# Power_board_1.net
KiCad netlist of a schematic drawn in Altium Designer
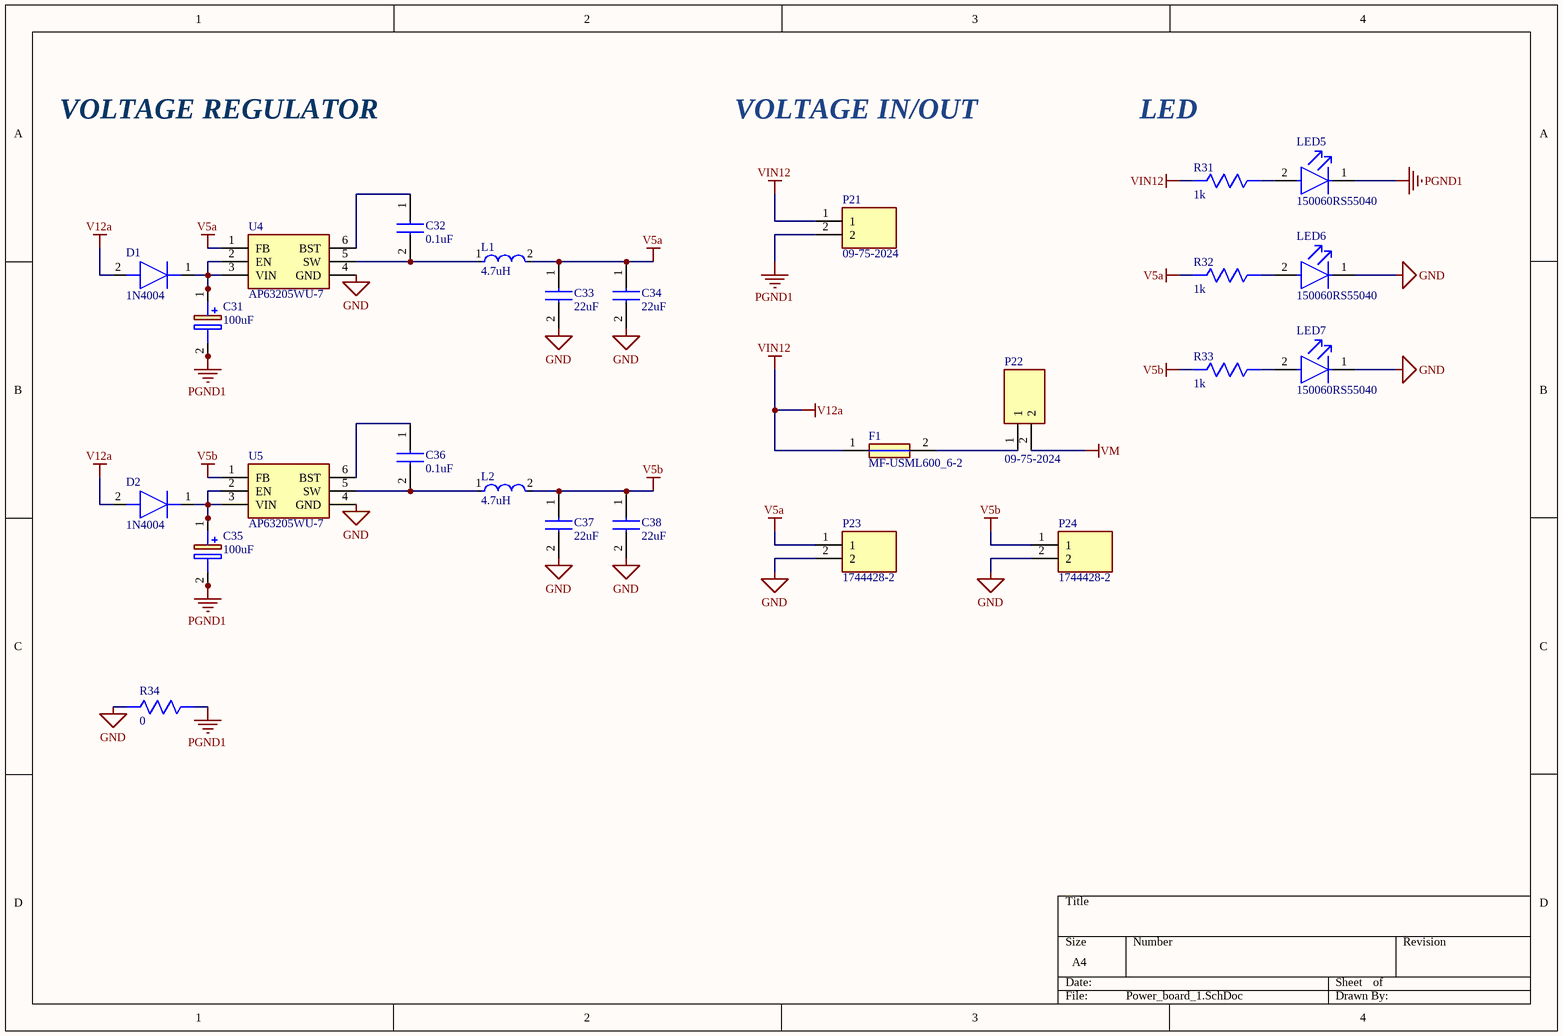
[diagram p0: Power_board_1.SchDoc]

(export (version "E")
  (design (tool "Eeschema 10.0.6"))
  (components
    (comp (ref "C31")
      (value "100uF")
      (footprint "SamacSys:CAPPM7344X310N")
      (description "Capacitor Polarised")
      (fields
        (field (name "MANUFACTURER_PART_NUMBER") "TAJD107K016RNJ")
        (field (name "MOUSER PART NUMBER") "581-TAJD107K016R")
      )
      (libsource (lib "*") (part "TAJD107K016RNJ"))
    )
    (comp (ref "C32")
      (value "0.1uF")
      (footprint "SamacSys:CAPC1608X90N")
      (description "Capacitor")
      (fields
        (field (name "MANUFACTURER_PART_NUMBER") "GRM188R72A104MA35D")
        (field (name "MOUSER PART NUMBER") "81-GRM188R72A104MA5D")
      )
      (libsource (lib "*") (part "GRM188R72A104MA35D"))
    )
    (comp (ref "C33")
      (value "22uF")
      (footprint "SamacSys:C1608_Commercial")
      (description "Capacitor")
      (fields (field (name "MANUFACTURER_PART_NUMBER") "C1608X5R1H104M080AA"))
      (libsource (lib "SamacSys") (part "C1608X5R1H104M080AA"))
    )
    (comp (ref "C34")
      (value "22uF")
      (footprint "SamacSys:C1608_Commercial")
      (description "Capacitor")
      (fields (field (name "MANUFACTURER_PART_NUMBER") "C1608X5R1H104M080AA"))
      (libsource (lib "SamacSys") (part "C1608X5R1H104M080AA"))
    )
    (comp (ref "C35")
      (value "100uF")
      (footprint "SamacSys:CAPPM7344X310N")
      (description "Capacitor Polarised")
      (fields
        (field (name "MANUFACTURER_PART_NUMBER") "TAJD107K016RNJ")
        (field (name "MOUSER PART NUMBER") "581-TAJD107K016R")
      )
      (libsource (lib "*") (part "TAJD107K016RNJ"))
    )
    (comp (ref "C36")
      (value "0.1uF")
      (footprint "SamacSys:CAPC1608X90N")
      (description "Capacitor")
      (fields
        (field (name "MANUFACTURER_PART_NUMBER") "GRM188R72A104MA35D")
        (field (name "MOUSER PART NUMBER") "81-GRM188R72A104MA5D")
      )
      (libsource (lib "*") (part "GRM188R72A104MA35D"))
    )
    (comp (ref "C37")
      (value "22uF")
      (footprint "SamacSys:C1608_Commercial")
      (description "Capacitor")
      (fields (field (name "MANUFACTURER_PART_NUMBER") "C1608X5R1H104M080AA"))
      (libsource (lib "SamacSys") (part "C1608X5R1H104M080AA"))
    )
    (comp (ref "C38")
      (value "22uF")
      (footprint "SamacSys:C1608_Commercial")
      (description "Capacitor")
      (fields (field (name "MANUFACTURER_PART_NUMBER") "C1608X5R1H104M080AA"))
      (libsource (lib "SamacSys") (part "C1608X5R1H104M080AA"))
    )
    (comp (ref "D1")
      (value "1N4004")
      (footprint "SamacSys:DIOAD1413W86L463D238")
      (description "Diode")
      (fields (field (name "MOUSER PART NUMBER") "863-1N4004"))
      (libsource (lib "*") (part "1N4004"))
    )
    (comp (ref "D2")
      (value "1N4004")
      (footprint "SamacSys:DIOAD1413W86L463D238")
      (description "Diode")
      (fields (field (name "MOUSER PART NUMBER") "863-1N4004"))
      (libsource (lib "*") (part "1N4004"))
    )
    (comp (ref "F1")
      (value "MF-USML600_6-2")
      (footprint "SamacSys:FUSC3226X120N")
      (description "Fuse")
      (fields
        (field (name "MANUFACTURER_PART_NUMBER") "MF-USML600/6-2")
        (field (name "MOUSER PART NUMBER") "652-MF-USML600/6-2")
      )
      (libsource (lib "*") (part "MF-USML600_6-2"))
    )
    (comp (ref "L1")
      (value "4.7uH")
      (footprint "FP-NR6028-MFG")
      (description "SMD Power Inductors for Automotive Applications 4.7uH ±20% 2.7A 40.3mΩ")
      (fields (field (name "TOLERANCE") "20%"))
      (libsource (lib "Altium Content Vault") (part "725321dda6339637d4d059423bc1c3c"))
    )
    (comp (ref "L2")
      (value "4.7uH")
      (footprint "FP-NR6028-MFG")
      (description "SMD Power Inductors for Automotive Applications 4.7uH ±20% 2.7A 40.3mΩ")
      (fields (field (name "TOLERANCE") "20%"))
      (libsource (lib "Altium Content Vault") (part "725321dda6339637d4d059423bc1c3c"))
    )
    (comp (ref "LED5")
      (value "150060RS55040")
      (footprint "FP-150060RS55040-MFG")
      (description "LED RED DIFFUSED 0603 SMD")
      (libsource (lib "Altium Content Vault") (part "8706943c75ba83719d021d2fdc84c58"))
    )
    (comp (ref "LED6")
      (value "150060RS55040")
      (footprint "FP-150060RS55040-MFG")
      (description "LED RED DIFFUSED 0603 SMD")
      (libsource (lib "Altium Content Vault") (part "8706943c75ba83719d021d2fdc84c58"))
    )
    (comp (ref "LED7")
      (value "150060RS55040")
      (footprint "FP-150060RS55040-MFG")
      (description "LED RED DIFFUSED 0603 SMD")
      (libsource (lib "Altium Content Vault") (part "8706943c75ba83719d021d2fdc84c58"))
    )
    (comp (ref "P21")
      (value "09-75-2024")
      (footprint "SamacSys:17444282")
      (description "Connector")
      (fields
        (field (name "MANUFACTURER_PART_NUMBER") "1744428-2")
        (field (name "MOUSER PART NUMBER") "571-1744428-2")
      )
      (libsource (lib "SamacSys") (part "1744428-2"))
    )
    (comp (ref "P22")
      (value "09-75-2024")
      (footprint "SamacSys:17444282")
      (description "Connector")
      (fields
        (field (name "MANUFACTURER_PART_NUMBER") "1744428-2")
        (field (name "MOUSER PART NUMBER") "571-1744428-2")
      )
      (libsource (lib "") (part "1744428-2_1"))
    )
    (comp (ref "P23")
      (value "1744428-2")
      (footprint "SamacSys:17444282")
      (description "Connector")
      (fields (field (name "MOUSER PART NUMBER") "571-1744428-2"))
      (libsource (lib "SamacSys") (part "1744428-2"))
    )
    (comp (ref "P24")
      (value "1744428-2")
      (footprint "SamacSys:17444282")
      (description "Connector")
      (fields (field (name "MOUSER PART NUMBER") "571-1744428-2"))
      (libsource (lib "SamacSys") (part "1744428-2"))
    )
    (comp (ref "R31")
      (value "1k")
      (footprint "SamacSys:RESC1608X55N")
      (description "Resistor")
      (fields (field (name "MANUFACTURER_PART_NUMBER") "CMP0603-FX-1003ELF"))
      (libsource (lib "SamacSys") (part "CMP0603-FX-1003ELF"))
    )
    (comp (ref "R32")
      (value "1k")
      (footprint "SamacSys:RESC1608X55N")
      (description "Resistor")
      (fields (field (name "MANUFACTURER_PART_NUMBER") "CMP0603-FX-1003ELF"))
      (libsource (lib "SamacSys") (part "CMP0603-FX-1003ELF"))
    )
    (comp (ref "R33")
      (value "1k")
      (footprint "SamacSys:RESC1608X55N")
      (description "Resistor")
      (fields (field (name "MANUFACTURER_PART_NUMBER") "CMP0603-FX-1003ELF"))
      (libsource (lib "SamacSys") (part "CMP0603-FX-1003ELF"))
    )
    (comp (ref "R34")
      (value "0")
      (footprint "SamacSys:RESC1608X55N")
      (description "Resistor")
      (fields (field (name "MANUFACTURER_PART_NUMBER") "CMP0603-FX-1003ELF"))
      (libsource (lib "SamacSys") (part "CMP0603-FX-1003ELF"))
    )
    (comp (ref "U4")
      (value "AP63205WU-7")
      (footprint "SamacSys:SOT95P280X100-6N")
      (description "Integrated Circuit")
      (fields (field (name "MOUSER PART NUMBER") "621-AP63205WU-7"))
      (libsource (lib "*") (part "AP63205WU-7"))
    )
    (comp (ref "U5")
      (value "AP63205WU-7")
      (footprint "SamacSys:SOT95P280X100-6N")
      (description "Integrated Circuit")
      (fields (field (name "MOUSER PART NUMBER") "621-AP63205WU-7"))
      (libsource (lib "*") (part "AP63205WU-7"))
    )
  )
  (nets
    (net (code "1") (name "GND") (class "Default")
      (node (ref "C33") (pin "2") (pinfunction "2_2") (pintype "passive"))
      (node (ref "C34") (pin "2") (pinfunction "2_2") (pintype "passive"))
      (node (ref "C37") (pin "2") (pinfunction "2_2") (pintype "passive"))
      (node (ref "C38") (pin "2") (pinfunction "2_2") (pintype "passive"))
      (node (ref "LED6") (pin "1") (pinfunction "C_1") (pintype "passive"))
      (node (ref "LED7") (pin "1") (pinfunction "C_1") (pintype "passive"))
      (node (ref "P23") (pin "2") (pinfunction "2_2") (pintype "passive"))
      (node (ref "P24") (pin "2") (pinfunction "2_2") (pintype "passive"))
      (node (ref "R34") (pin "1") (pinfunction "1_1") (pintype "passive"))
      (node (ref "U4") (pin "4") (pinfunction "GND_4") (pintype "passive"))
      (node (ref "U5") (pin "4") (pinfunction "GND_4") (pintype "passive"))
    )
    (net (code "2") (name "Net-(C31-+)") (class "Default")
      (node (ref "C31") (pin "1") (pinfunction "+_1") (pintype "passive"))
      (node (ref "D1") (pin "1") (pinfunction "K_1") (pintype "passive"))
      (node (ref "U4") (pin "2") (pinfunction "EN_2") (pintype "passive"))
      (node (ref "U4") (pin "3") (pinfunction "VIN_3") (pintype "passive"))
    )
    (net (code "3") (name "Net-(C35-+)") (class "Default")
      (node (ref "C35") (pin "1") (pinfunction "+_1") (pintype "passive"))
      (node (ref "D2") (pin "1") (pinfunction "K_1") (pintype "passive"))
      (node (ref "U5") (pin "2") (pinfunction "EN_2") (pintype "passive"))
      (node (ref "U5") (pin "3") (pinfunction "VIN_3") (pintype "passive"))
    )
    (net (code "4") (name "Net-(F1-Pad2)") (class "Default")
      (node (ref "F1") (pin "2") (pinfunction "2_2") (pintype "passive"))
      (node (ref "P22") (pin "1") (pinfunction "1_1") (pintype "passive"))
    )
    (net (code "5") (name "Net-(LED5-A)") (class "Default")
      (node (ref "LED5") (pin "2") (pinfunction "A_2") (pintype "passive"))
      (node (ref "R31") (pin "2") (pinfunction "2_2") (pintype "passive"))
    )
    (net (code "6") (name "Net-(LED6-A)") (class "Default")
      (node (ref "LED6") (pin "2") (pinfunction "A_2") (pintype "passive"))
      (node (ref "R32") (pin "2") (pinfunction "2_2") (pintype "passive"))
    )
    (net (code "7") (name "Net-(LED7-A)") (class "Default")
      (node (ref "LED7") (pin "2") (pinfunction "A_2") (pintype "passive"))
      (node (ref "R33") (pin "2") (pinfunction "2_2") (pintype "passive"))
    )
    (net (code "8") (name "Net-(U4-BST)") (class "Default")
      (node (ref "C32") (pin "1") (pinfunction "1_1") (pintype "passive"))
      (node (ref "U4") (pin "6") (pinfunction "BST_6") (pintype "passive"))
    )
    (net (code "9") (name "Net-(U4-SW)") (class "Default")
      (node (ref "C32") (pin "2") (pinfunction "2_2") (pintype "passive"))
      (node (ref "L1") (pin "1") (pinfunction "1_1") (pintype "passive"))
      (node (ref "U4") (pin "5") (pinfunction "SW_5") (pintype "passive"))
    )
    (net (code "10") (name "Net-(U5-BST)") (class "Default")
      (node (ref "C36") (pin "1") (pinfunction "1_1") (pintype "passive"))
      (node (ref "U5") (pin "6") (pinfunction "BST_6") (pintype "passive"))
    )
    (net (code "11") (name "Net-(U5-SW)") (class "Default")
      (node (ref "C36") (pin "2") (pinfunction "2_2") (pintype "passive"))
      (node (ref "L2") (pin "1") (pinfunction "1_1") (pintype "passive"))
      (node (ref "U5") (pin "5") (pinfunction "SW_5") (pintype "passive"))
    )
    (net (code "12") (name "PGND1") (class "Default")
      (node (ref "C31") (pin "2") (pinfunction "-_2") (pintype "passive"))
      (node (ref "C35") (pin "2") (pinfunction "-_2") (pintype "passive"))
      (node (ref "LED5") (pin "1") (pinfunction "C_1") (pintype "passive"))
      (node (ref "P21") (pin "2") (pinfunction "2_2") (pintype "passive"))
      (node (ref "R34") (pin "2") (pinfunction "2_2") (pintype "passive"))
    )
    (net (code "13") (name "V5a") (class "Default")
      (node (ref "C33") (pin "1") (pinfunction "1_1") (pintype "passive"))
      (node (ref "C34") (pin "1") (pinfunction "1_1") (pintype "passive"))
      (node (ref "L1") (pin "2") (pinfunction "2_2") (pintype "passive"))
      (node (ref "P23") (pin "1") (pinfunction "1_1") (pintype "passive"))
      (node (ref "R32") (pin "1") (pinfunction "1_1") (pintype "passive"))
      (node (ref "U4") (pin "1") (pinfunction "FB_1") (pintype "passive"))
    )
    (net (code "14") (name "V5b") (class "Default")
      (node (ref "C37") (pin "1") (pinfunction "1_1") (pintype "passive"))
      (node (ref "C38") (pin "1") (pinfunction "1_1") (pintype "passive"))
      (node (ref "L2") (pin "2") (pinfunction "2_2") (pintype "passive"))
      (node (ref "P24") (pin "1") (pinfunction "1_1") (pintype "passive"))
      (node (ref "R33") (pin "1") (pinfunction "1_1") (pintype "passive"))
      (node (ref "U5") (pin "1") (pinfunction "FB_1") (pintype "passive"))
    )
    (net (code "15") (name "V12a") (class "Default")
      (node (ref "D1") (pin "2") (pinfunction "A_2") (pintype "passive"))
      (node (ref "D2") (pin "2") (pinfunction "A_2") (pintype "passive"))
      (node (ref "F1") (pin "1") (pinfunction "1_1") (pintype "passive"))
      (node (ref "P21") (pin "1") (pinfunction "1_1") (pintype "passive"))
      (node (ref "R31") (pin "1") (pinfunction "1_1") (pintype "passive"))
    )
    (net (code "16") (name "VM") (class "Default")
      (node (ref "P22") (pin "2") (pinfunction "2_2") (pintype "passive"))
    )
  )
)
